# DigBMPproto.net
KiCad netlist of a schematic drawn in EAGLE
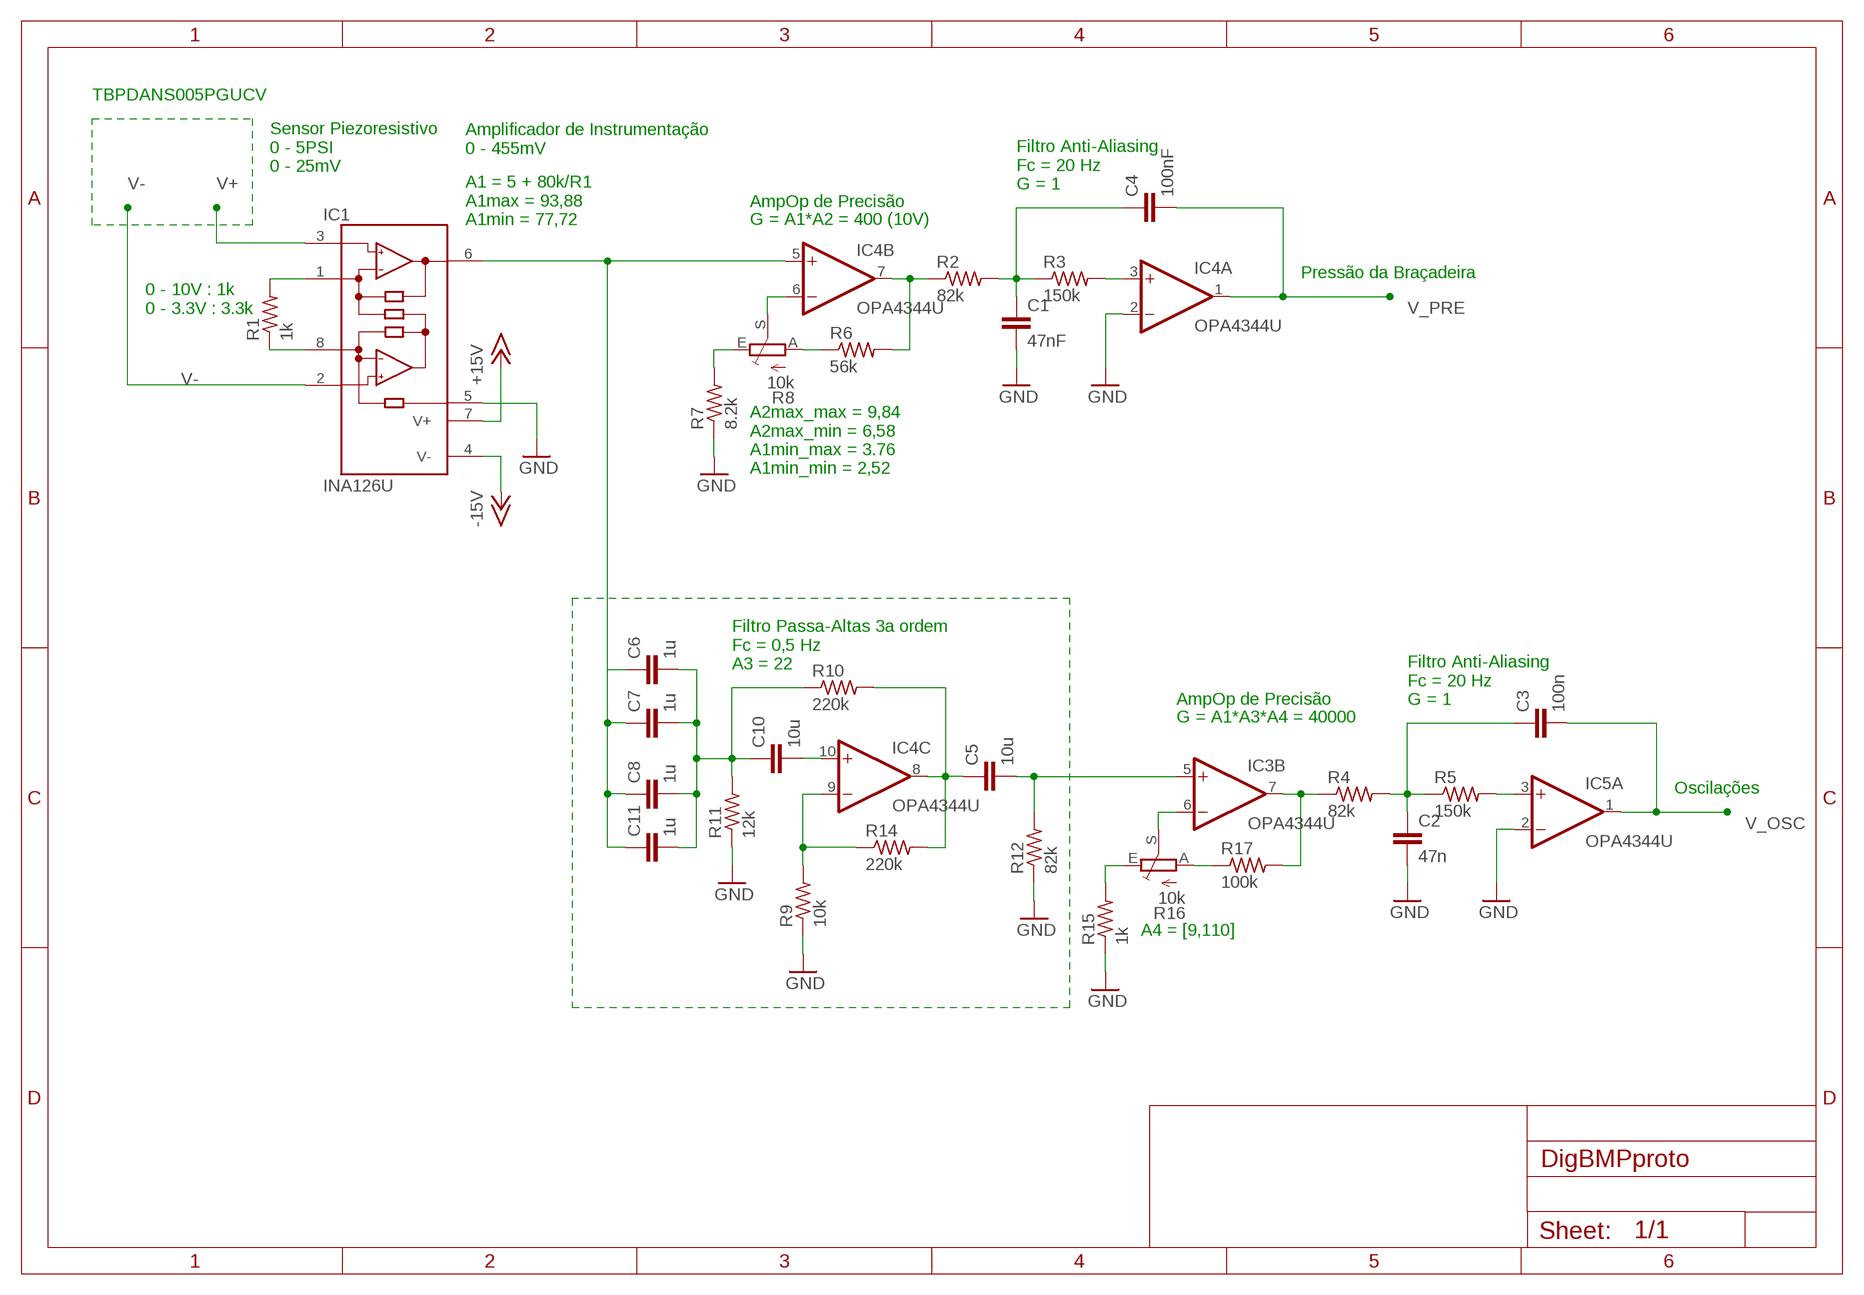
[diagram p0: schematic, sheet 1]

(export (version "E")
  (design (tool "Eeschema 10.0.6"))
  (components
    (comp (ref "C1")
      (value "47nF")
      (footprint "eagle-import:C3216")
      (libsource (lib "eagle-import") (part "C-EUC3216"))
    )
    (comp (ref "C2")
      (value "47n")
      (footprint "eagle-import:C3216")
      (libsource (lib "eagle-import") (part "C-EUC3216"))
    )
    (comp (ref "C3")
      (value "100n")
      (footprint "eagle-import:C3216")
      (libsource (lib "eagle-import") (part "C-EUC3216"))
    )
    (comp (ref "C4")
      (value "100nF")
      (footprint "eagle-import:C3216")
      (libsource (lib "eagle-import") (part "C-EUC3216"))
    )
    (comp (ref "C5")
      (value "10u")
      (footprint "eagle-import:C3216")
      (libsource (lib "eagle-import") (part "C-EUC3216"))
    )
    (comp (ref "C6")
      (value "1u")
      (footprint "eagle-import:C3216")
      (libsource (lib "eagle-import") (part "C-EUC3216"))
    )
    (comp (ref "C7")
      (value "1u")
      (footprint "eagle-import:C3216")
      (libsource (lib "eagle-import") (part "C-EUC3216"))
    )
    (comp (ref "C8")
      (value "1u")
      (footprint "eagle-import:C3216")
      (libsource (lib "eagle-import") (part "C-EUC3216"))
    )
    (comp (ref "C10")
      (value "10u")
      (footprint "eagle-import:C3216")
      (libsource (lib "eagle-import") (part "C-EUC3216"))
    )
    (comp (ref "C11")
      (value "1u")
      (footprint "eagle-import:C3216")
      (libsource (lib "eagle-import") (part "C-EUC3216"))
    )
    (comp (ref "IC1")
      (value "INA126U")
      (footprint "eagle-import:SO08")
      (fields (field (name "MF") "TEXAS INSTRUMENTS"))
      (libsource (lib "eagle-import") (part "INA126U"))
    )
    (comp (ref "IC3")
      (value "OPA4344U")
      (footprint "eagle-import:SO14")
      (libsource (lib "eagle-import") (part "OPA4U344"))
    )
    (comp (ref "IC4")
      (value "OPA4344U")
      (footprint "eagle-import:SO14")
      (libsource (lib "eagle-import") (part "OPA4U344"))
    )
    (comp (ref "IC5")
      (value "OPA4344U")
      (footprint "eagle-import:SO14")
      (libsource (lib "eagle-import") (part "OPA4U344"))
    )
    (comp (ref "R1")
      (value "1k")
      (footprint "eagle-import:M1206")
      (libsource (lib "eagle-import") (part "R-US_M1206"))
    )
    (comp (ref "R2")
      (value "82k")
      (footprint "eagle-import:M1206")
      (libsource (lib "eagle-import") (part "R-US_M1206"))
    )
    (comp (ref "R3")
      (value "150k")
      (footprint "eagle-import:M1206")
      (libsource (lib "eagle-import") (part "R-US_M1206"))
    )
    (comp (ref "R4")
      (value "82k")
      (footprint "eagle-import:M1206")
      (libsource (lib "eagle-import") (part "R-US_M1206"))
    )
    (comp (ref "R5")
      (value "150k")
      (footprint "eagle-import:M1206")
      (libsource (lib "eagle-import") (part "R-US_M1206"))
    )
    (comp (ref "R6")
      (value "56k")
      (footprint "eagle-import:M1206")
      (libsource (lib "eagle-import") (part "R-US_M1206"))
    )
    (comp (ref "R7")
      (value "8.2k")
      (footprint "eagle-import:M1206")
      (libsource (lib "eagle-import") (part "R-US_M1206"))
    )
    (comp (ref "R8")
      (value "10k")
      (footprint "eagle-import:B64Y")
      (libsource (lib "eagle-import") (part "TRIM_EU-B64Y"))
    )
    (comp (ref "R9")
      (value "10k")
      (footprint "eagle-import:M1206")
      (libsource (lib "eagle-import") (part "R-US_M1206"))
    )
    (comp (ref "R10")
      (value "220k")
      (footprint "eagle-import:M1206")
      (libsource (lib "eagle-import") (part "R-US_M1206"))
    )
    (comp (ref "R11")
      (value "12k")
      (footprint "eagle-import:M1206")
      (libsource (lib "eagle-import") (part "R-US_M1206"))
    )
    (comp (ref "R12")
      (value "82k")
      (footprint "eagle-import:M1206")
      (libsource (lib "eagle-import") (part "R-US_M1206"))
    )
    (comp (ref "R14")
      (value "220k")
      (footprint "eagle-import:M1206")
      (libsource (lib "eagle-import") (part "R-US_M1206"))
    )
    (comp (ref "R15")
      (value "1k")
      (footprint "eagle-import:M1206")
      (libsource (lib "eagle-import") (part "R-US_M1206"))
    )
    (comp (ref "R16")
      (value "10k")
      (footprint "eagle-import:B64Y")
      (libsource (lib "eagle-import") (part "TRIM_EU-B64Y"))
    )
    (comp (ref "R17")
      (value "100k")
      (footprint "eagle-import:M1206")
      (libsource (lib "eagle-import") (part "R-US_M1206"))
    )
  )
  (nets
    (net (code "1") (name "+15V") (class "Default")
      (node (ref "IC1") (pin "7") (pinfunction "V+_7") (pintype "power_in"))
    )
    (net (code "2") (name "-15V") (class "Default")
      (node (ref "IC1") (pin "4") (pinfunction "V-_4") (pintype "power_in"))
    )
    (net (code "3") (name "/V+") (class "Default")
      (node (ref "IC1") (pin "3") (pinfunction "+IN_3") (pintype "input"))
    )
    (net (code "4") (name "/V-") (class "Default")
      (node (ref "IC1") (pin "2") (pinfunction "-IN_2") (pintype "input"))
    )
    (net (code "5") (name "/V_OSC") (class "Default")
      (node (ref "C3") (pin "2") (pinfunction "2_2") (pintype "passive"))
      (node (ref "IC5") (pin "1") (pinfunction "OUT_1") (pintype "output"))
    )
    (net (code "6") (name "/V_PRE") (class "Default")
      (node (ref "C4") (pin "2") (pinfunction "2_2") (pintype "passive"))
      (node (ref "IC4") (pin "1") (pinfunction "OUT_1") (pintype "output"))
    )
    (net (code "7") (name "GND") (class "Default")
      (node (ref "C1") (pin "2") (pinfunction "2_2") (pintype "passive"))
      (node (ref "C2") (pin "2") (pinfunction "2_2") (pintype "passive"))
      (node (ref "IC1") (pin "5") (pinfunction "REF_5") (pintype "passive"))
      (node (ref "IC4") (pin "2") (pinfunction "-IN_2") (pintype "input"))
      (node (ref "IC5") (pin "2") (pinfunction "-IN_2") (pintype "input"))
      (node (ref "R11") (pin "1") (pinfunction "1_1") (pintype "passive"))
      (node (ref "R12") (pin "1") (pinfunction "1_1") (pintype "passive"))
      (node (ref "R15") (pin "1") (pinfunction "1_1") (pintype "passive"))
      (node (ref "R7") (pin "1") (pinfunction "1_1") (pintype "passive"))
      (node (ref "R9") (pin "1") (pinfunction "1_1") (pintype "passive"))
    )
    (net (code "8") (name "Net-(C1-Pad1)") (class "Default")
      (node (ref "C1") (pin "1") (pinfunction "1_1") (pintype "passive"))
      (node (ref "C4") (pin "1") (pinfunction "1_1") (pintype "passive"))
      (node (ref "R2") (pin "2") (pinfunction "2_2") (pintype "passive"))
      (node (ref "R3") (pin "1") (pinfunction "1_1") (pintype "passive"))
    )
    (net (code "9") (name "Net-(C2-Pad1)") (class "Default")
      (node (ref "C2") (pin "1") (pinfunction "1_1") (pintype "passive"))
      (node (ref "C3") (pin "1") (pinfunction "1_1") (pintype "passive"))
      (node (ref "R4") (pin "2") (pinfunction "2_2") (pintype "passive"))
      (node (ref "R5") (pin "1") (pinfunction "1_1") (pintype "passive"))
    )
    (net (code "10") (name "Net-(C10-Pad1)") (class "Default")
      (node (ref "C10") (pin "1") (pinfunction "1_1") (pintype "passive"))
      (node (ref "C11") (pin "2") (pinfunction "2_2") (pintype "passive"))
      (node (ref "C6") (pin "2") (pinfunction "2_2") (pintype "passive"))
      (node (ref "C7") (pin "2") (pinfunction "2_2") (pintype "passive"))
      (node (ref "C8") (pin "2") (pinfunction "2_2") (pintype "passive"))
      (node (ref "R10") (pin "1") (pinfunction "1_1") (pintype "passive"))
      (node (ref "R11") (pin "2") (pinfunction "2_2") (pintype "passive"))
    )
    (net (code "11") (name "Net-(IC1-OUT)") (class "Default")
      (node (ref "C11") (pin "1") (pinfunction "1_1") (pintype "passive"))
      (node (ref "C6") (pin "1") (pinfunction "1_1") (pintype "passive"))
      (node (ref "C7") (pin "1") (pinfunction "1_1") (pintype "passive"))
      (node (ref "C8") (pin "1") (pinfunction "1_1") (pintype "passive"))
      (node (ref "IC1") (pin "6") (pinfunction "OUT_6") (pintype "output"))
      (node (ref "IC4") (pin "5") (pinfunction "+IN_5") (pintype "input"))
    )
    (net (code "12") (name "Net-(IC1-RG-Pad1)") (class "Default")
      (node (ref "IC1") (pin "1") (pinfunction "RG_1") (pintype "passive"))
      (node (ref "R1") (pin "2") (pinfunction "2_2") (pintype "passive"))
    )
    (net (code "13") (name "Net-(IC1-RG-Pad8)") (class "Default")
      (node (ref "IC1") (pin "8") (pinfunction "RG_8") (pintype "passive"))
      (node (ref "R1") (pin "1") (pinfunction "1_1") (pintype "passive"))
    )
    (net (code "14") (name "Net-(IC3B-+IN)") (class "Default")
      (node (ref "C5") (pin "2") (pinfunction "2_2") (pintype "passive"))
      (node (ref "IC3") (pin "5") (pinfunction "+IN_5") (pintype "input"))
      (node (ref "R12") (pin "2") (pinfunction "2_2") (pintype "passive"))
    )
    (net (code "15") (name "Net-(IC3B--IN)") (class "Default")
      (node (ref "IC3") (pin "6") (pinfunction "-IN_6") (pintype "input"))
      (node (ref "R16") (pin "S") (pinfunction "S_S") (pintype "passive"))
    )
    (net (code "16") (name "Net-(IC3B-OUT)") (class "Default")
      (node (ref "IC3") (pin "7") (pinfunction "OUT_7") (pintype "output"))
      (node (ref "R17") (pin "2") (pinfunction "2_2") (pintype "passive"))
      (node (ref "R4") (pin "1") (pinfunction "1_1") (pintype "passive"))
    )
    (net (code "17") (name "Net-(IC4A-+IN)") (class "Default")
      (node (ref "IC4") (pin "3") (pinfunction "+IN_3") (pintype "input"))
      (node (ref "R3") (pin "2") (pinfunction "2_2") (pintype "passive"))
    )
    (net (code "18") (name "Net-(IC4B--IN)") (class "Default")
      (node (ref "IC4") (pin "6") (pinfunction "-IN_6") (pintype "input"))
      (node (ref "R8") (pin "S") (pinfunction "S_S") (pintype "passive"))
    )
    (net (code "19") (name "Net-(IC4B-OUT)") (class "Default")
      (node (ref "IC4") (pin "7") (pinfunction "OUT_7") (pintype "output"))
      (node (ref "R2") (pin "1") (pinfunction "1_1") (pintype "passive"))
      (node (ref "R6") (pin "2") (pinfunction "2_2") (pintype "passive"))
    )
    (net (code "20") (name "Net-(IC4C-+IN)") (class "Default")
      (node (ref "C10") (pin "2") (pinfunction "2_2") (pintype "passive"))
      (node (ref "IC4") (pin "10") (pinfunction "+IN_10") (pintype "input"))
    )
    (net (code "21") (name "Net-(IC4C--IN)") (class "Default")
      (node (ref "IC4") (pin "9") (pinfunction "-IN_9") (pintype "input"))
      (node (ref "R14") (pin "1") (pinfunction "1_1") (pintype "passive"))
      (node (ref "R9") (pin "2") (pinfunction "2_2") (pintype "passive"))
    )
    (net (code "22") (name "Net-(IC4C-OUT)") (class "Default")
      (node (ref "C5") (pin "1") (pinfunction "1_1") (pintype "passive"))
      (node (ref "IC4") (pin "8") (pinfunction "OUT_8") (pintype "output"))
      (node (ref "R10") (pin "2") (pinfunction "2_2") (pintype "passive"))
      (node (ref "R14") (pin "2") (pinfunction "2_2") (pintype "passive"))
    )
    (net (code "23") (name "Net-(IC5A-+IN)") (class "Default")
      (node (ref "IC5") (pin "3") (pinfunction "+IN_3") (pintype "input"))
      (node (ref "R5") (pin "2") (pinfunction "2_2") (pintype "passive"))
    )
    (net (code "24") (name "Net-(R6-Pad1)") (class "Default")
      (node (ref "R6") (pin "1") (pinfunction "1_1") (pintype "passive"))
      (node (ref "R8") (pin "A") (pinfunction "A_A") (pintype "passive"))
    )
    (net (code "25") (name "Net-(R7-Pad2)") (class "Default")
      (node (ref "R7") (pin "2") (pinfunction "2_2") (pintype "passive"))
      (node (ref "R8") (pin "E") (pinfunction "E_E") (pintype "passive"))
    )
    (net (code "26") (name "Net-(R15-Pad2)") (class "Default")
      (node (ref "R15") (pin "2") (pinfunction "2_2") (pintype "passive"))
      (node (ref "R16") (pin "E") (pinfunction "E_E") (pintype "passive"))
    )
    (net (code "27") (name "Net-(R16-PadA)") (class "Default")
      (node (ref "R16") (pin "A") (pinfunction "A_A") (pintype "passive"))
      (node (ref "R17") (pin "1") (pinfunction "1_1") (pintype "passive"))
    )
  )
)
